# MicroBit_Robot_Interface_RevD.net
KiCad netlist of a schematic drawn in EAGLE
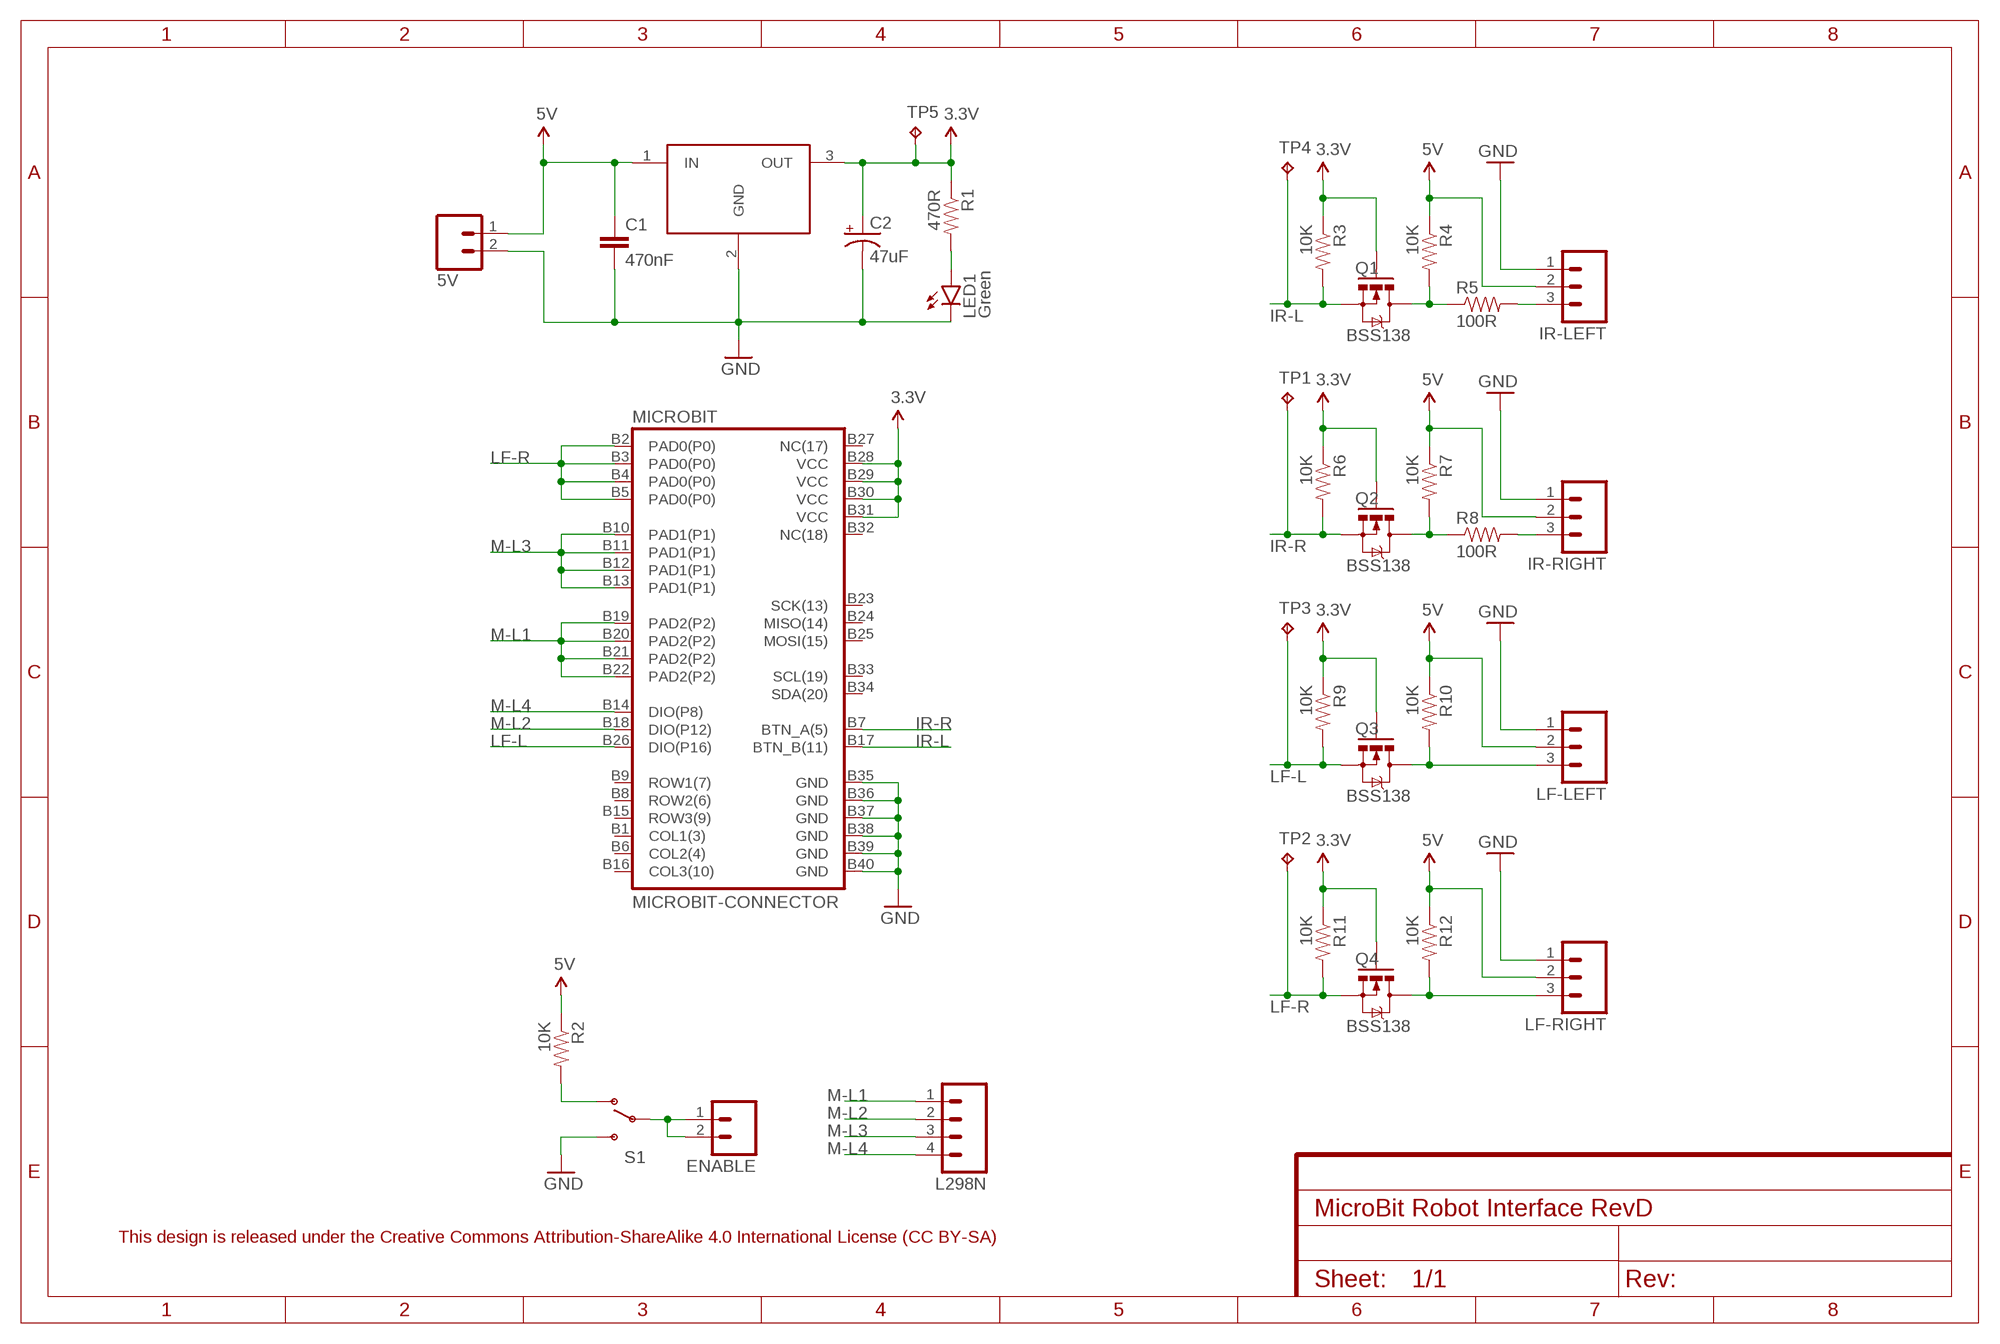
[diagram p0: schematic, sheet 1]

(export (version "E")
  (design (tool "Eeschema 10.0.6"))
  (components
    (comp (ref "5V")
      (value "MCOMP_SCREWTERM_2PIN5MM")
      (footprint "eagle-import:MCOMP-SCREWTERMINAL-5MM-2")
      (libsource (lib "eagle-import") (part "MCOMP_SCREWTERM_2PIN5MM"))
    )
    (comp (ref "C1")
      (value "470nF")
      (footprint "eagle-import:0603-CAP")
      (libsource (lib "eagle-import") (part "CAP0603-CAP"))
    )
    (comp (ref "C2")
      (value "47uF")
      (footprint "eagle-import:CPOL-RADIAL-100UF-25V")
      (libsource (lib "eagle-import") (part "CAP_POLPTH1"))
    )
    (comp (ref "ENABLE")
      (value "M02PTH")
      (footprint "eagle-import:1X02")
      (libsource (lib "eagle-import") (part "M02PTH"))
    )
    (comp (ref "IR-LEFT")
      (value "M03PTH")
      (footprint "eagle-import:1X03")
      (libsource (lib "eagle-import") (part "M03PTH"))
    )
    (comp (ref "IR-RIGHT")
      (value "M03PTH")
      (footprint "eagle-import:1X03")
      (libsource (lib "eagle-import") (part "M03PTH"))
    )
    (comp (ref "L298N")
      (value "M04PTH")
      (footprint "eagle-import:1X04")
      (libsource (lib "eagle-import") (part "M04PTH"))
    )
    (comp (ref "LED1")
      (value "Green")
      (footprint "eagle-import:LED3MM")
      (libsource (lib "eagle-import") (part "LED3MM"))
    )
    (comp (ref "LF-LEFT")
      (value "M03PTH")
      (footprint "eagle-import:1X03")
      (libsource (lib "eagle-import") (part "M03PTH"))
    )
    (comp (ref "LF-RIGHT")
      (value "M03PTH")
      (footprint "eagle-import:1X03")
      (libsource (lib "eagle-import") (part "M03PTH"))
    )
    (comp (ref "MICROBIT")
      (value "MICROBIT-CONNECTOR")
      (footprint "eagle-import:RBB40DHHN_MICROBIT")
      (libsource (lib "eagle-import") (part "MICROBIT-CONNECTOR"))
    )
    (comp (ref "Q1")
      (value "BSS138")
      (footprint "eagle-import:SOT23-3")
      (libsource (lib "eagle-import") (part "MOSFET-NCHANNELBSS138"))
    )
    (comp (ref "Q2")
      (value "BSS138")
      (footprint "eagle-import:SOT23-3")
      (libsource (lib "eagle-import") (part "MOSFET-NCHANNELBSS138"))
    )
    (comp (ref "Q3")
      (value "BSS138")
      (footprint "eagle-import:SOT23-3")
      (libsource (lib "eagle-import") (part "MOSFET-NCHANNELBSS138"))
    )
    (comp (ref "Q4")
      (value "BSS138")
      (footprint "eagle-import:SOT23-3")
      (libsource (lib "eagle-import") (part "MOSFET-NCHANNELBSS138"))
    )
    (comp (ref "R1")
      (value "470R")
      (footprint "eagle-import:0603-RES")
      (libsource (lib "eagle-import") (part "RESISTOR0603-RES"))
    )
    (comp (ref "R2")
      (value "10K")
      (footprint "eagle-import:0603-RES")
      (libsource (lib "eagle-import") (part "RESISTOR0603-RES"))
    )
    (comp (ref "R3")
      (value "10K")
      (footprint "eagle-import:0603-RES")
      (libsource (lib "eagle-import") (part "RESISTOR0603-RES"))
    )
    (comp (ref "R4")
      (value "10K")
      (footprint "eagle-import:0603-RES")
      (libsource (lib "eagle-import") (part "RESISTOR0603-RES"))
    )
    (comp (ref "R5")
      (value "100R")
      (footprint "eagle-import:0603-RES")
      (libsource (lib "eagle-import") (part "RESISTOR0603-RES"))
    )
    (comp (ref "R6")
      (value "10K")
      (footprint "eagle-import:0603-RES")
      (libsource (lib "eagle-import") (part "RESISTOR0603-RES"))
    )
    (comp (ref "R7")
      (value "10K")
      (footprint "eagle-import:0603-RES")
      (libsource (lib "eagle-import") (part "RESISTOR0603-RES"))
    )
    (comp (ref "R8")
      (value "100R")
      (footprint "eagle-import:0603-RES")
      (libsource (lib "eagle-import") (part "RESISTOR0603-RES"))
    )
    (comp (ref "R9")
      (value "10K")
      (footprint "eagle-import:0603-RES")
      (libsource (lib "eagle-import") (part "RESISTOR0603-RES"))
    )
    (comp (ref "R10")
      (value "10K")
      (footprint "eagle-import:0603-RES")
      (libsource (lib "eagle-import") (part "RESISTOR0603-RES"))
    )
    (comp (ref "R11")
      (value "10K")
      (footprint "eagle-import:0603-RES")
      (libsource (lib "eagle-import") (part "RESISTOR0603-RES"))
    )
    (comp (ref "R12")
      (value "10K")
      (footprint "eagle-import:0603-RES")
      (libsource (lib "eagle-import") (part "RESISTOR0603-RES"))
    )
    (comp (ref "S1")
      (value "KNITTER-SWITCH-MFP106D")
      (footprint "eagle-import:KNITTER-SWITCH-MFP106D")
      (libsource (lib "eagle-import") (part "KNITTER-SWITCH-MFP106D"))
    )
    (comp (ref "TP1")
      (value "TPTP10R")
      (footprint "eagle-import:TP10R")
      (libsource (lib "eagle-import") (part "TPTP10R"))
    )
    (comp (ref "TP2")
      (value "TPTP10R")
      (footprint "eagle-import:TP10R")
      (libsource (lib "eagle-import") (part "TPTP10R"))
    )
    (comp (ref "TP3")
      (value "TPTP10R")
      (footprint "eagle-import:TP10R")
      (libsource (lib "eagle-import") (part "TPTP10R"))
    )
    (comp (ref "TP4")
      (value "TPTP10R")
      (footprint "eagle-import:TP10R")
      (libsource (lib "eagle-import") (part "TPTP10R"))
    )
    (comp (ref "TP5")
      (value "TPTP10R")
      (footprint "eagle-import:TP10R")
      (libsource (lib "eagle-import") (part "TPTP10R"))
    )
    (comp (ref "VR1")
      (value "LM3940IMP-3.3")
      (footprint "eagle-import:SOT223")
      (libsource (lib "eagle-import") (part "LM3940IMP-3.3"))
    )
  )
  (nets
    (net (code "1") (name "/IR-L") (class "Default")
      (node (ref "MICROBIT") (pin "B17") (pinfunction "BTN_B(11)_B17") (pintype "input"))
      (node (ref "Q1") (pin "2") (pinfunction "S_2") (pintype "passive"))
      (node (ref "R3") (pin "2") (pinfunction "2_2") (pintype "passive"))
      (node (ref "TP4") (pin "TP") (pinfunction "TP_TP") (pintype "input"))
    )
    (net (code "2") (name "/IR-R") (class "Default")
      (node (ref "MICROBIT") (pin "B7") (pinfunction "BTN_A(5)_B7") (pintype "input"))
      (node (ref "Q2") (pin "2") (pinfunction "S_2") (pintype "passive"))
      (node (ref "R6") (pin "2") (pinfunction "2_2") (pintype "passive"))
      (node (ref "TP1") (pin "TP") (pinfunction "TP_TP") (pintype "input"))
    )
    (net (code "3") (name "/LF-L") (class "Default")
      (node (ref "MICROBIT") (pin "B26") (pinfunction "DIO(P16)_B26") (pintype "bidirectional"))
      (node (ref "Q3") (pin "2") (pinfunction "S_2") (pintype "passive"))
      (node (ref "R9") (pin "2") (pinfunction "2_2") (pintype "passive"))
      (node (ref "TP3") (pin "TP") (pinfunction "TP_TP") (pintype "input"))
    )
    (net (code "4") (name "/LF-R") (class "Default")
      (node (ref "MICROBIT") (pin "B2") (pinfunction "PAD0(P0)_B2") (pintype "bidirectional"))
      (node (ref "MICROBIT") (pin "B3") (pinfunction "PAD0(P0)_B3") (pintype "bidirectional"))
      (node (ref "MICROBIT") (pin "B4") (pinfunction "PAD0(P0)_B4") (pintype "bidirectional"))
      (node (ref "MICROBIT") (pin "B5") (pinfunction "PAD0(P0)_B5") (pintype "bidirectional"))
      (node (ref "Q4") (pin "2") (pinfunction "S_2") (pintype "passive"))
      (node (ref "R11") (pin "2") (pinfunction "2_2") (pintype "passive"))
      (node (ref "TP2") (pin "TP") (pinfunction "TP_TP") (pintype "input"))
    )
    (net (code "5") (name "/M-L1") (class "Default")
      (node (ref "L298N") (pin "1") (pinfunction "1_1") (pintype "passive"))
      (node (ref "MICROBIT") (pin "B19") (pinfunction "PAD2(P2)_B19") (pintype "bidirectional"))
      (node (ref "MICROBIT") (pin "B20") (pinfunction "PAD2(P2)_B20") (pintype "bidirectional"))
      (node (ref "MICROBIT") (pin "B21") (pinfunction "PAD2(P2)_B21") (pintype "bidirectional"))
      (node (ref "MICROBIT") (pin "B22") (pinfunction "PAD2(P2)_B22") (pintype "bidirectional"))
    )
    (net (code "6") (name "/M-L2") (class "Default")
      (node (ref "L298N") (pin "2") (pinfunction "2_2") (pintype "passive"))
      (node (ref "MICROBIT") (pin "B18") (pinfunction "DIO(P12)_B18") (pintype "bidirectional"))
    )
    (net (code "7") (name "/M-L3") (class "Default")
      (node (ref "L298N") (pin "3") (pinfunction "3_3") (pintype "passive"))
      (node (ref "MICROBIT") (pin "B10") (pinfunction "PAD1(P1)_B10") (pintype "bidirectional"))
      (node (ref "MICROBIT") (pin "B11") (pinfunction "PAD1(P1)_B11") (pintype "bidirectional"))
      (node (ref "MICROBIT") (pin "B12") (pinfunction "PAD1(P1)_B12") (pintype "bidirectional"))
      (node (ref "MICROBIT") (pin "B13") (pinfunction "PAD1(P1)_B13") (pintype "bidirectional"))
    )
    (net (code "8") (name "/M-L4") (class "Default")
      (node (ref "L298N") (pin "4") (pinfunction "4_4") (pintype "passive"))
      (node (ref "MICROBIT") (pin "B14") (pinfunction "DIO(P8)_B14") (pintype "bidirectional"))
    )
    (net (code "9") (name "3.3V") (class "Default")
      (node (ref "C2") (pin "1") (pinfunction "+_1") (pintype "passive"))
      (node (ref "MICROBIT") (pin "B28") (pinfunction "VCC_B28") (pintype "power_in"))
      (node (ref "MICROBIT") (pin "B29") (pinfunction "VCC_B29") (pintype "power_in"))
      (node (ref "MICROBIT") (pin "B30") (pinfunction "VCC_B30") (pintype "power_in"))
      (node (ref "MICROBIT") (pin "B31") (pinfunction "VCC_B31") (pintype "power_in"))
      (node (ref "Q1") (pin "1") (pinfunction "G_1") (pintype "passive"))
      (node (ref "Q2") (pin "1") (pinfunction "G_1") (pintype "passive"))
      (node (ref "Q3") (pin "1") (pinfunction "G_1") (pintype "passive"))
      (node (ref "Q4") (pin "1") (pinfunction "G_1") (pintype "passive"))
      (node (ref "R1") (pin "1") (pinfunction "1_1") (pintype "passive"))
      (node (ref "R11") (pin "1") (pinfunction "1_1") (pintype "passive"))
      (node (ref "R3") (pin "1") (pinfunction "1_1") (pintype "passive"))
      (node (ref "R6") (pin "1") (pinfunction "1_1") (pintype "passive"))
      (node (ref "R9") (pin "1") (pinfunction "1_1") (pintype "passive"))
      (node (ref "TP5") (pin "TP") (pinfunction "TP_TP") (pintype "input"))
      (node (ref "VR1") (pin "3") (pinfunction "OUT_3") (pintype "power_in"))
    )
    (net (code "10") (name "5V") (class "Default")
      (node (ref "5V") (pin "1") (pinfunction "1_1") (pintype "passive"))
      (node (ref "C1") (pin "1") (pinfunction "1_1") (pintype "passive"))
      (node (ref "IR-LEFT") (pin "2") (pinfunction "2_2") (pintype "passive"))
      (node (ref "IR-RIGHT") (pin "2") (pinfunction "2_2") (pintype "passive"))
      (node (ref "LF-LEFT") (pin "2") (pinfunction "2_2") (pintype "passive"))
      (node (ref "LF-RIGHT") (pin "2") (pinfunction "2_2") (pintype "passive"))
      (node (ref "R10") (pin "1") (pinfunction "1_1") (pintype "passive"))
      (node (ref "R12") (pin "1") (pinfunction "1_1") (pintype "passive"))
      (node (ref "R2") (pin "1") (pinfunction "1_1") (pintype "passive"))
      (node (ref "R4") (pin "1") (pinfunction "1_1") (pintype "passive"))
      (node (ref "R7") (pin "1") (pinfunction "1_1") (pintype "passive"))
      (node (ref "VR1") (pin "1") (pinfunction "IN_1") (pintype "power_in"))
    )
    (net (code "11") (name "GND") (class "Default")
      (node (ref "5V") (pin "2") (pinfunction "2_2") (pintype "passive"))
      (node (ref "C1") (pin "2") (pinfunction "2_2") (pintype "passive"))
      (node (ref "C2") (pin "2") (pinfunction "-_2") (pintype "passive"))
      (node (ref "IR-LEFT") (pin "1") (pinfunction "1_1") (pintype "passive"))
      (node (ref "IR-RIGHT") (pin "1") (pinfunction "1_1") (pintype "passive"))
      (node (ref "LED1") (pin "K") (pinfunction "C_K") (pintype "passive"))
      (node (ref "LF-LEFT") (pin "1") (pinfunction "1_1") (pintype "passive"))
      (node (ref "LF-RIGHT") (pin "1") (pinfunction "1_1") (pintype "passive"))
      (node (ref "MICROBIT") (pin "B35") (pinfunction "GND_B35") (pintype "power_in"))
      (node (ref "MICROBIT") (pin "B36") (pinfunction "GND_B36") (pintype "power_in"))
      (node (ref "MICROBIT") (pin "B37") (pinfunction "GND_B37") (pintype "power_in"))
      (node (ref "MICROBIT") (pin "B38") (pinfunction "GND_B38") (pintype "power_in"))
      (node (ref "MICROBIT") (pin "B39") (pinfunction "GND_B39") (pintype "power_in"))
      (node (ref "MICROBIT") (pin "B40") (pinfunction "GND_B40") (pintype "power_in"))
      (node (ref "S1") (pin "P$2") (pinfunction "POS2_P$2") (pintype "passive"))
      (node (ref "VR1") (pin "2") (pinfunction "GND_2") (pintype "power_in"))
    )
    (net (code "12") (name "Net-(IR-LEFT-Pad3)") (class "Default")
      (node (ref "IR-LEFT") (pin "3") (pinfunction "3_3") (pintype "passive"))
      (node (ref "R5") (pin "2") (pinfunction "2_2") (pintype "passive"))
    )
    (net (code "13") (name "Net-(IR-RIGHT-Pad3)") (class "Default")
      (node (ref "IR-RIGHT") (pin "3") (pinfunction "3_3") (pintype "passive"))
      (node (ref "R8") (pin "2") (pinfunction "2_2") (pintype "passive"))
    )
    (net (code "14") (name "Net-(LED1-PadA)") (class "Default")
      (node (ref "LED1") (pin "A") (pinfunction "A_A") (pintype "passive"))
      (node (ref "R1") (pin "2") (pinfunction "2_2") (pintype "passive"))
    )
    (net (code "15") (name "Net-(Q1-D)") (class "Default")
      (node (ref "Q1") (pin "3") (pinfunction "D_3") (pintype "passive"))
      (node (ref "R4") (pin "2") (pinfunction "2_2") (pintype "passive"))
      (node (ref "R5") (pin "1") (pinfunction "1_1") (pintype "passive"))
    )
    (net (code "16") (name "Net-(Q2-D)") (class "Default")
      (node (ref "Q2") (pin "3") (pinfunction "D_3") (pintype "passive"))
      (node (ref "R7") (pin "2") (pinfunction "2_2") (pintype "passive"))
      (node (ref "R8") (pin "1") (pinfunction "1_1") (pintype "passive"))
    )
    (net (code "17") (name "Net-(Q3-D)") (class "Default")
      (node (ref "LF-LEFT") (pin "3") (pinfunction "3_3") (pintype "passive"))
      (node (ref "Q3") (pin "3") (pinfunction "D_3") (pintype "passive"))
      (node (ref "R10") (pin "2") (pinfunction "2_2") (pintype "passive"))
    )
    (net (code "18") (name "Net-(Q4-D)") (class "Default")
      (node (ref "LF-RIGHT") (pin "3") (pinfunction "3_3") (pintype "passive"))
      (node (ref "Q4") (pin "3") (pinfunction "D_3") (pintype "passive"))
      (node (ref "R12") (pin "2") (pinfunction "2_2") (pintype "passive"))
    )
    (net (code "19") (name "Net-(S1-COMMON)") (class "Default")
      (node (ref "ENABLE") (pin "1") (pinfunction "1_1") (pintype "passive"))
      (node (ref "ENABLE") (pin "2") (pinfunction "2_2") (pintype "passive"))
      (node (ref "S1") (pin "WIPER") (pinfunction "COMMON_WIPER") (pintype "passive"))
    )
    (net (code "20") (name "Net-(S1-POS1)") (class "Default")
      (node (ref "R2") (pin "2") (pinfunction "2_2") (pintype "passive"))
      (node (ref "S1") (pin "P$1") (pinfunction "POS1_P$1") (pintype "passive"))
    )
    (net (code "21") (name "unconnected-(MICROBIT-COL1(3)-PadB1)") (class "Default")
      (node (ref "MICROBIT") (pin "B1") (pinfunction "COL1(3)_B1") (pintype "output"))
    )
    (net (code "22") (name "unconnected-(MICROBIT-COL2(4)-PadB6)") (class "Default")
      (node (ref "MICROBIT") (pin "B6") (pinfunction "COL2(4)_B6") (pintype "output"))
    )
    (net (code "23") (name "unconnected-(MICROBIT-COL3(10)-PadB16)") (class "Default")
      (node (ref "MICROBIT") (pin "B16") (pinfunction "COL3(10)_B16") (pintype "output"))
    )
    (net (code "24") (name "unconnected-(MICROBIT-MISO(14)-PadB24)") (class "Default")
      (node (ref "MICROBIT") (pin "B24") (pinfunction "MISO(14)_B24") (pintype "bidirectional"))
    )
    (net (code "25") (name "unconnected-(MICROBIT-MOSI(15)-PadB25)") (class "Default")
      (node (ref "MICROBIT") (pin "B25") (pinfunction "MOSI(15)_B25") (pintype "bidirectional"))
    )
    (net (code "26") (name "unconnected-(MICROBIT-NC(17)-PadB27)") (class "Default")
      (node (ref "MICROBIT") (pin "B27") (pinfunction "NC(17)_B27") (pintype "no_connect"))
    )
    (net (code "27") (name "unconnected-(MICROBIT-NC(18)-PadB32)") (class "Default")
      (node (ref "MICROBIT") (pin "B32") (pinfunction "NC(18)_B32") (pintype "no_connect"))
    )
    (net (code "28") (name "unconnected-(MICROBIT-ROW1(7)-PadB9)") (class "Default")
      (node (ref "MICROBIT") (pin "B9") (pinfunction "ROW1(7)_B9") (pintype "output"))
    )
    (net (code "29") (name "unconnected-(MICROBIT-ROW2(6)-PadB8)") (class "Default")
      (node (ref "MICROBIT") (pin "B8") (pinfunction "ROW2(6)_B8") (pintype "output"))
    )
    (net (code "30") (name "unconnected-(MICROBIT-ROW3(9)-PadB15)") (class "Default")
      (node (ref "MICROBIT") (pin "B15") (pinfunction "ROW3(9)_B15") (pintype "output"))
    )
    (net (code "31") (name "unconnected-(MICROBIT-SCK(13)-PadB23)") (class "Default")
      (node (ref "MICROBIT") (pin "B23") (pinfunction "SCK(13)_B23") (pintype "bidirectional"))
    )
    (net (code "32") (name "unconnected-(MICROBIT-SCL(19)-PadB33)") (class "Default")
      (node (ref "MICROBIT") (pin "B33") (pinfunction "SCL(19)_B33") (pintype "bidirectional"))
    )
    (net (code "33") (name "unconnected-(MICROBIT-SDA(20)-PadB34)") (class "Default")
      (node (ref "MICROBIT") (pin "B34") (pinfunction "SDA(20)_B34") (pintype "bidirectional"))
    )
  )
)
